# OLED_Adapter_ein_Display2.net
KiCad netlist of a schematic drawn in EAGLE
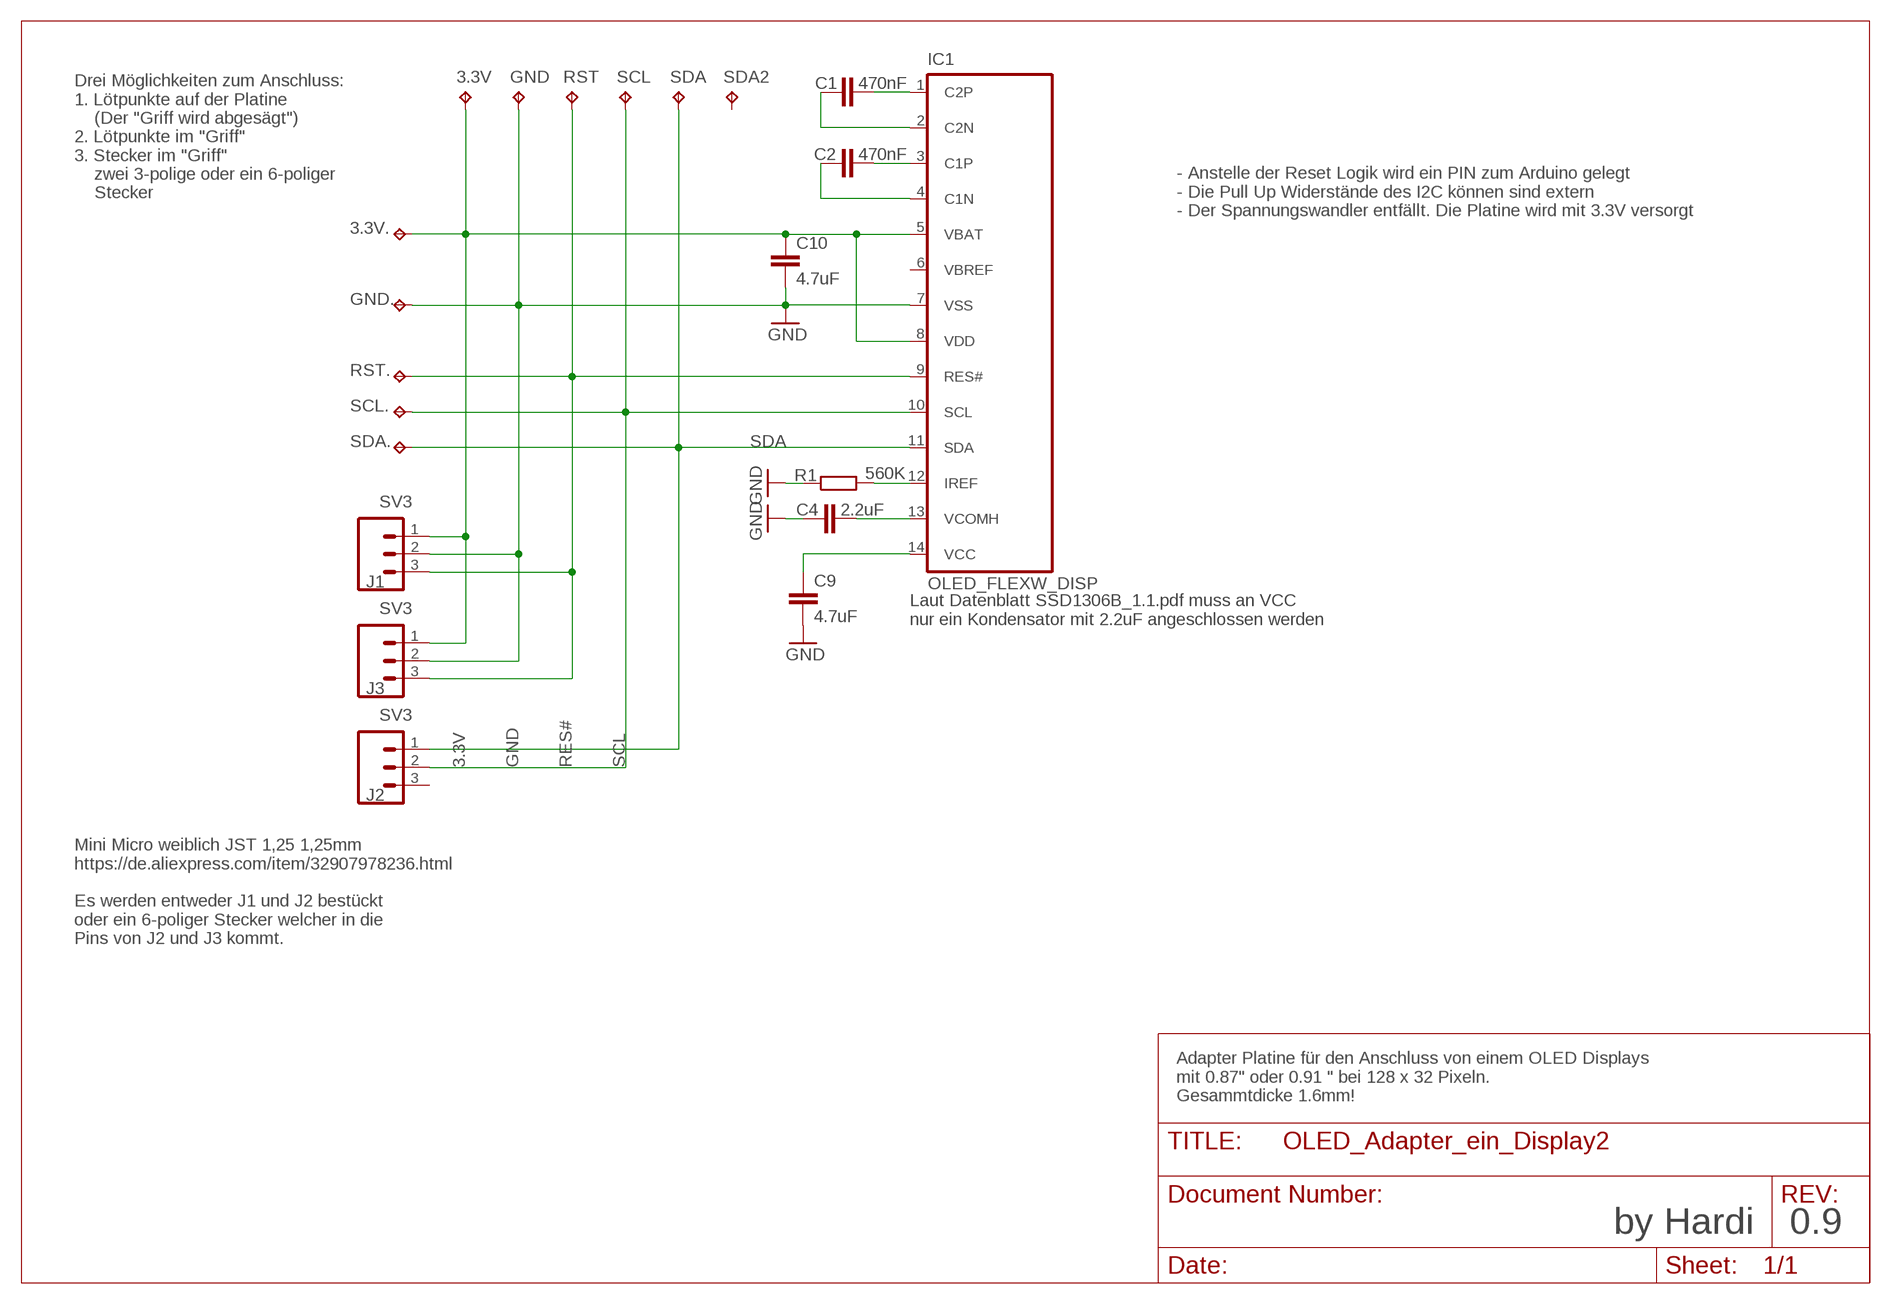
[diagram p0: schematic, sheet 1]

(export (version "E")
  (design (tool "Eeschema 10.0.6"))
  (components
    (comp (ref "3.3V")
      (value "3.3V")
      (footprint "eagle-import:TP16SQ")
      (libsource (lib "eagle-import") (part "TPTP16SQ"))
    )
    (comp (ref "3.3V.")
      (value "TPTP16SQ")
      (footprint "eagle-import:TP16SQ")
      (libsource (lib "eagle-import") (part "TPTP16SQ"))
    )
    (comp (ref "C1")
      (value "470nF")
      (footprint "eagle-import:C0603")
      (libsource (lib "eagle-import") (part "C-EUC0603"))
    )
    (comp (ref "C2")
      (value "470nF")
      (footprint "eagle-import:C0603")
      (libsource (lib "eagle-import") (part "C-EUC0603"))
    )
    (comp (ref "C4")
      (value "2.2uF")
      (footprint "eagle-import:C0603")
      (libsource (lib "eagle-import") (part "C-EUC0603"))
    )
    (comp (ref "C9")
      (value "4.7uF")
      (footprint "eagle-import:C0603")
      (libsource (lib "eagle-import") (part "C-EUC0603"))
    )
    (comp (ref "C10")
      (value "4.7uF")
      (footprint "eagle-import:C0603")
      (libsource (lib "eagle-import") (part "C-EUC0603"))
    )
    (comp (ref "GND")
      (value "GND")
      (footprint "eagle-import:TP16R")
      (libsource (lib "eagle-import") (part "TPTP16R"))
    )
    (comp (ref "GND.")
      (value "TPTP16R")
      (footprint "eagle-import:TP16R")
      (libsource (lib "eagle-import") (part "TPTP16R"))
    )
    (comp (ref "IC1")
      (value "OLED_FLEXW_DISP")
      (footprint "eagle-import:OLED_FLEX_W_DISP")
      (libsource (lib "eagle-import") (part "OLED_FLEXW_DISP"))
    )
    (comp (ref "J1")
      (value "SV3")
      (footprint "eagle-import:MINI")
      (libsource (lib "eagle-import") (part "M03"))
    )
    (comp (ref "J2")
      (value "SV3")
      (footprint "eagle-import:MINI")
      (libsource (lib "eagle-import") (part "M03"))
    )
    (comp (ref "J3")
      (value "SV3")
      (footprint "eagle-import:MINI")
      (libsource (lib "eagle-import") (part "M03"))
    )
    (comp (ref "R1")
      (value "560K")
      (footprint "eagle-import:R0603")
      (libsource (lib "eagle-import") (part "R-EU_R0603"))
    )
    (comp (ref "RST")
      (value "RST")
      (footprint "eagle-import:TP16R")
      (libsource (lib "eagle-import") (part "TPTP16R"))
    )
    (comp (ref "RST.")
      (value "TPTP16R")
      (footprint "eagle-import:TP16R")
      (libsource (lib "eagle-import") (part "TPTP16R"))
    )
    (comp (ref "SCL")
      (value "SCL")
      (footprint "eagle-import:TP16R")
      (libsource (lib "eagle-import") (part "TPTP16R"))
    )
    (comp (ref "SCL.")
      (value "TPTP16R")
      (footprint "eagle-import:TP16R")
      (libsource (lib "eagle-import") (part "TPTP16R"))
    )
    (comp (ref "SDA")
      (value "SDA")
      (footprint "eagle-import:TP16R")
      (libsource (lib "eagle-import") (part "TPTP16R"))
    )
    (comp (ref "SDA.")
      (value "TPTP16R")
      (footprint "eagle-import:TP16R")
      (libsource (lib "eagle-import") (part "TPTP16R"))
    )
    (comp (ref "SDA2")
      (value "SDA2")
      (footprint "eagle-import:TP16R")
      (libsource (lib "eagle-import") (part "TPTP16R"))
    )
  )
  (nets
    (net (code "1") (name "/3.3V") (class "Default")
      (node (ref "3.3V") (pin "TP") (pinfunction "TP_TP") (pintype "input"))
      (node (ref "3.3V.") (pin "TP") (pinfunction "TP_TP") (pintype "input"))
      (node (ref "C10") (pin "1") (pinfunction "1_1") (pintype "passive"))
      (node (ref "IC1") (pin "5") (pinfunction "VBAT_5") (pintype "power_in"))
      (node (ref "IC1") (pin "8") (pinfunction "VDD_8") (pintype "power_in"))
      (node (ref "J1") (pin "1") (pinfunction "1_1") (pintype "passive"))
      (node (ref "J3") (pin "1") (pinfunction "1_1") (pintype "passive"))
    )
    (net (code "2") (name "/RES#") (class "Default")
      (node (ref "IC1") (pin "9") (pinfunction "RES#_9") (pintype "input"))
      (node (ref "J1") (pin "3") (pinfunction "3_3") (pintype "passive"))
      (node (ref "J3") (pin "3") (pinfunction "3_3") (pintype "passive"))
      (node (ref "RST") (pin "TP") (pinfunction "TP_TP") (pintype "input"))
      (node (ref "RST.") (pin "TP") (pinfunction "TP_TP") (pintype "input"))
    )
    (net (code "3") (name "/SCL") (class "Default")
      (node (ref "IC1") (pin "10") (pinfunction "SCL_10") (pintype "bidirectional"))
      (node (ref "J2") (pin "2") (pinfunction "2_2") (pintype "passive"))
      (node (ref "SCL") (pin "TP") (pinfunction "TP_TP") (pintype "input"))
      (node (ref "SCL.") (pin "TP") (pinfunction "TP_TP") (pintype "input"))
    )
    (net (code "4") (name "/SDA") (class "Default")
      (node (ref "IC1") (pin "11") (pinfunction "SDA_11") (pintype "bidirectional"))
      (node (ref "J2") (pin "1") (pinfunction "1_1") (pintype "passive"))
      (node (ref "SDA") (pin "TP") (pinfunction "TP_TP") (pintype "input"))
      (node (ref "SDA.") (pin "TP") (pinfunction "TP_TP") (pintype "input"))
    )
    (net (code "5") (name "GND") (class "Default")
      (node (ref "C10") (pin "2") (pinfunction "2_2") (pintype "passive"))
      (node (ref "C4") (pin "1") (pinfunction "1_1") (pintype "passive"))
      (node (ref "C9") (pin "2") (pinfunction "2_2") (pintype "passive"))
      (node (ref "GND") (pin "TP") (pinfunction "TP_TP") (pintype "input"))
      (node (ref "GND.") (pin "TP") (pinfunction "TP_TP") (pintype "input"))
      (node (ref "IC1") (pin "7") (pinfunction "VSS_7") (pintype "power_in"))
      (node (ref "J1") (pin "2") (pinfunction "2_2") (pintype "passive"))
      (node (ref "J3") (pin "2") (pinfunction "2_2") (pintype "passive"))
      (node (ref "R1") (pin "1") (pinfunction "1_1") (pintype "passive"))
    )
    (net (code "6") (name "Net-(IC1-C1N)") (class "Default")
      (node (ref "C2") (pin "1") (pinfunction "1_1") (pintype "passive"))
      (node (ref "IC1") (pin "4") (pinfunction "C1N_4") (pintype "bidirectional"))
    )
    (net (code "7") (name "Net-(IC1-C1P)") (class "Default")
      (node (ref "C2") (pin "2") (pinfunction "2_2") (pintype "passive"))
      (node (ref "IC1") (pin "3") (pinfunction "C1P_3") (pintype "bidirectional"))
    )
    (net (code "8") (name "Net-(IC1-C2N)") (class "Default")
      (node (ref "C1") (pin "1") (pinfunction "1_1") (pintype "passive"))
      (node (ref "IC1") (pin "2") (pinfunction "C2N_2") (pintype "bidirectional"))
    )
    (net (code "9") (name "Net-(IC1-C2P)") (class "Default")
      (node (ref "C1") (pin "2") (pinfunction "2_2") (pintype "passive"))
      (node (ref "IC1") (pin "1") (pinfunction "C2P_1") (pintype "bidirectional"))
    )
    (net (code "10") (name "Net-(IC1-IREF)") (class "Default")
      (node (ref "IC1") (pin "12") (pinfunction "IREF_12") (pintype "input"))
      (node (ref "R1") (pin "2") (pinfunction "2_2") (pintype "passive"))
    )
    (net (code "11") (name "Net-(IC1-VCC)") (class "Default")
      (node (ref "C9") (pin "1") (pinfunction "1_1") (pintype "passive"))
      (node (ref "IC1") (pin "14") (pinfunction "VCC_14") (pintype "power_in"))
    )
    (net (code "12") (name "Net-(IC1-VCOMH)") (class "Default")
      (node (ref "C4") (pin "2") (pinfunction "2_2") (pintype "passive"))
      (node (ref "IC1") (pin "13") (pinfunction "VCOMH_13") (pintype "input"))
    )
    (net (code "13") (name "unconnected-(IC1-VBREF-Pad6)") (class "Default")
      (node (ref "IC1") (pin "6") (pinfunction "VBREF_6") (pintype "input"))
    )
    (net (code "14") (name "unconnected-(J2-Pad3)") (class "Default")
      (node (ref "J2") (pin "3") (pinfunction "3_3") (pintype "passive"))
    )
    (net (code "15") (name "unconnected-(SDA2-PadTP)") (class "Default")
      (node (ref "SDA2") (pin "TP") (pinfunction "TP_TP") (pintype "input"))
    )
  )
)
